# L298.net
KiCad netlist of a schematic drawn in EAGLE
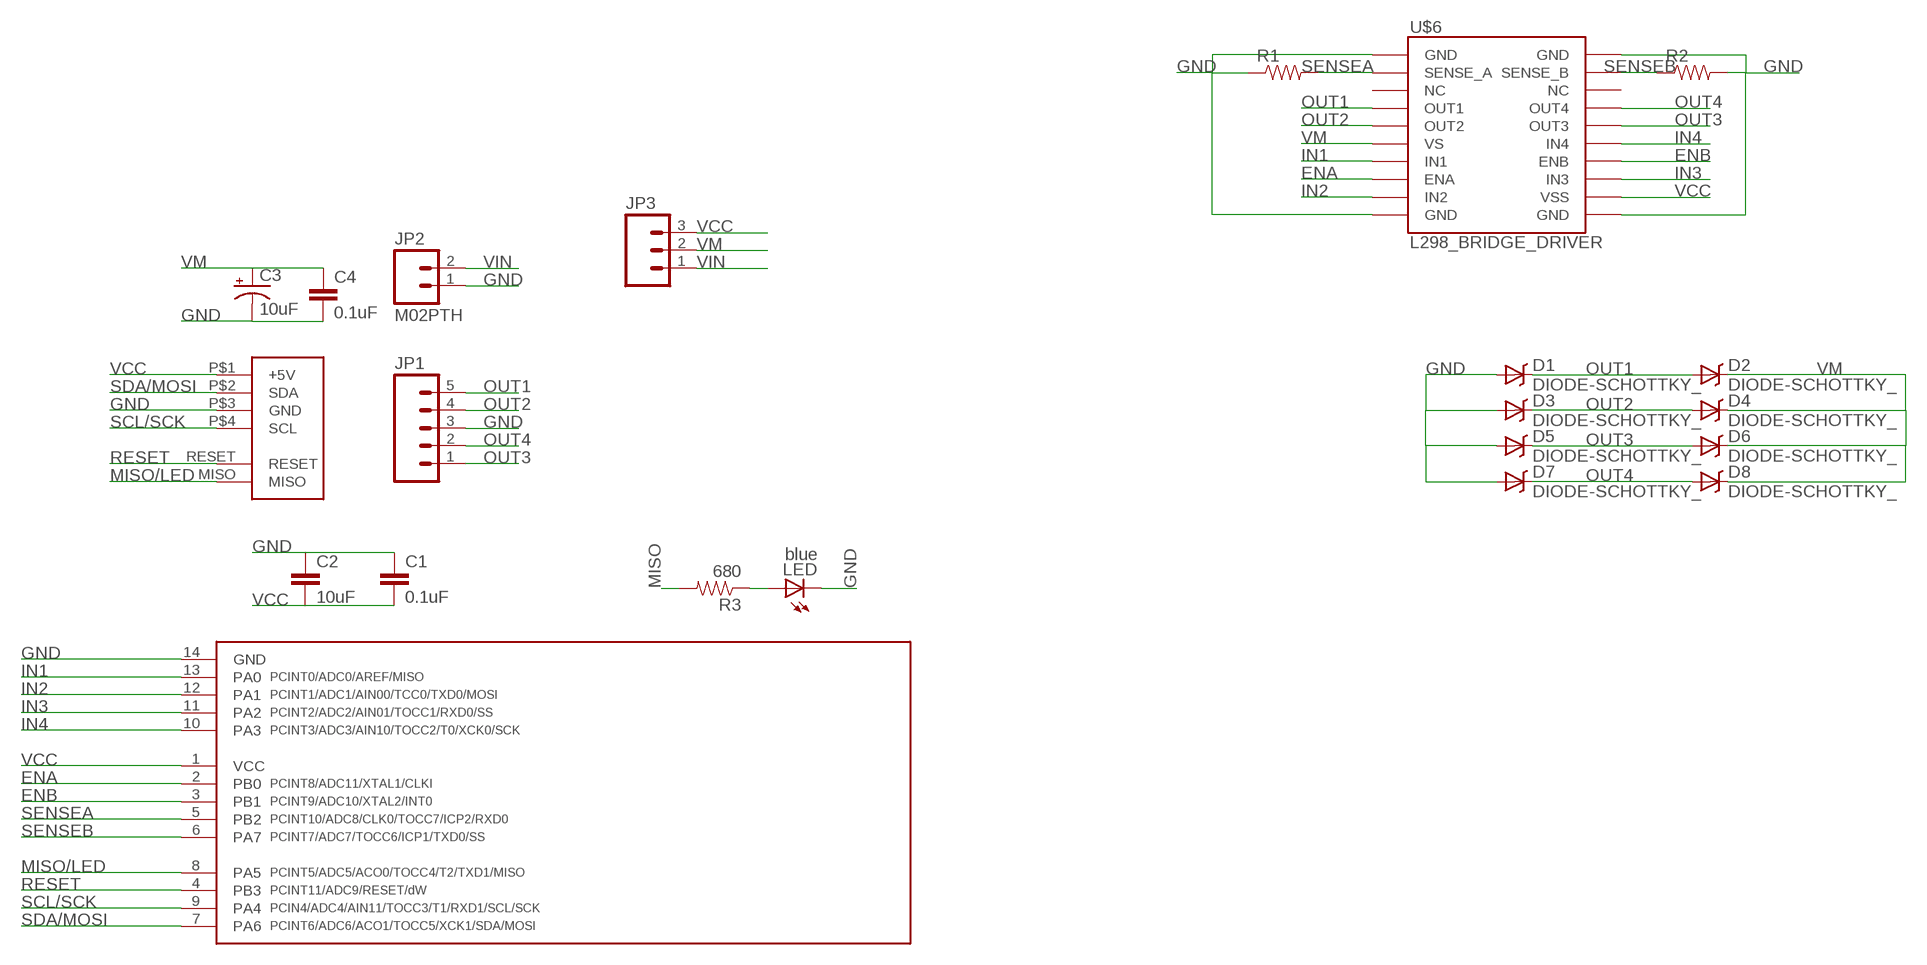
[diagram p0: schematic, sheet 1]

(export (version "E")
  (design (tool "Eeschema 10.0.6"))
  (components
    (comp (ref "C1")
      (value "0.1uF")
      (footprint "eagle-import:0805")
      (libsource (lib "eagle-import") (part "CAP0805"))
    )
    (comp (ref "C2")
      (value "10uF")
      (footprint "eagle-import:0805")
      (libsource (lib "eagle-import") (part "CAP0805"))
    )
    (comp (ref "C3")
      (value "10uF")
      (footprint "eagle-import:PANASONIC_D")
      (libsource (lib "eagle-import") (part "CAP_POLD"))
    )
    (comp (ref "C4")
      (value "0.1uF")
      (footprint "eagle-import:0805")
      (libsource (lib "eagle-import") (part "CAP0805"))
    )
    (comp (ref "D1")
      (value "DIODE-SCHOTTKY_")
      (footprint "eagle-import:SMA-DIODE")
      (libsource (lib "eagle-import") (part "DIODE-SCHOTTKY_"))
    )
    (comp (ref "D2")
      (value "DIODE-SCHOTTKY_")
      (footprint "eagle-import:SMA-DIODE")
      (libsource (lib "eagle-import") (part "DIODE-SCHOTTKY_"))
    )
    (comp (ref "D3")
      (value "DIODE-SCHOTTKY_")
      (footprint "eagle-import:SMA-DIODE")
      (libsource (lib "eagle-import") (part "DIODE-SCHOTTKY_"))
    )
    (comp (ref "D4")
      (value "DIODE-SCHOTTKY_")
      (footprint "eagle-import:SMA-DIODE")
      (libsource (lib "eagle-import") (part "DIODE-SCHOTTKY_"))
    )
    (comp (ref "D5")
      (value "DIODE-SCHOTTKY_")
      (footprint "eagle-import:SMA-DIODE")
      (libsource (lib "eagle-import") (part "DIODE-SCHOTTKY_"))
    )
    (comp (ref "D6")
      (value "DIODE-SCHOTTKY_")
      (footprint "eagle-import:SMA-DIODE")
      (libsource (lib "eagle-import") (part "DIODE-SCHOTTKY_"))
    )
    (comp (ref "D7")
      (value "DIODE-SCHOTTKY_")
      (footprint "eagle-import:SMA-DIODE")
      (libsource (lib "eagle-import") (part "DIODE-SCHOTTKY_"))
    )
    (comp (ref "D8")
      (value "DIODE-SCHOTTKY_")
      (footprint "eagle-import:SMA-DIODE")
      (libsource (lib "eagle-import") (part "DIODE-SCHOTTKY_"))
    )
    (comp (ref "JP1")
      (value "M05PTH")
      (footprint "eagle-import:1X05")
      (libsource (lib "eagle-import") (part "M05PTH"))
    )
    (comp (ref "JP2")
      (value "M02PTH")
      (footprint "eagle-import:1X02")
      (libsource (lib "eagle-import") (part "M02PTH"))
    )
    (comp (ref "JP3")
      (value "M03PTH")
      (footprint "eagle-import:1X03")
      (libsource (lib "eagle-import") (part "M03PTH"))
    )
    (comp (ref "LED")
      (value "blue")
      (footprint "eagle-import:CHIPLED_1206")
      (libsource (lib "eagle-import") (part "LEDCHIPLED_1206"))
    )
    (comp (ref "R1")
      (value "RESISTOR0805-RES")
      (footprint "eagle-import:0805")
      (libsource (lib "eagle-import") (part "SparkFun-Resistors_RESISTOR0805-RES"))
    )
    (comp (ref "R2")
      (value "RESISTOR0805-RES")
      (footprint "eagle-import:0805")
      (libsource (lib "eagle-import") (part "SparkFun-Resistors_RESISTOR0805-RES"))
    )
    (comp (ref "R3")
      (value "680")
      (footprint "eagle-import:0805")
      (libsource (lib "eagle-import") (part "RESISTOR0805-RES"))
    )
    (comp (ref "U$3")
      (value "TINY841")
      (footprint "eagle-import:SOIC14")
      (libsource (lib "eagle-import") (part "TINY841"))
    )
    (comp (ref "U$4")
      (value "FOOTPRINT")
      (footprint "eagle-import:FOOTPRINT")
      (libsource (lib "eagle-import") (part "FOOTPRINT"))
    )
    (comp (ref "U$6")
      (value "L298_BRIDGE_DRIVER")
      (footprint "eagle-import:POWERSO20")
      (libsource (lib "eagle-import") (part "L298_BRIDGE_DRIVER"))
    )
  )
  (nets
    (net (code "1") (name "/ENA") (class "Default")
      (node (ref "U$3") (pin "2") (pinfunction "PB0_2") (pintype "bidirectional"))
      (node (ref "U$6") (pin "8") (pinfunction "ENA_8") (pintype "bidirectional"))
    )
    (net (code "2") (name "/ENB") (class "Default")
      (node (ref "U$3") (pin "3") (pinfunction "PB1_3") (pintype "bidirectional"))
      (node (ref "U$6") (pin "14") (pinfunction "ENB_14") (pintype "bidirectional"))
    )
    (net (code "3") (name "/GND") (class "Default")
      (node (ref "C1") (pin "1") (pinfunction "1_1") (pintype "passive"))
      (node (ref "C2") (pin "1") (pinfunction "1_1") (pintype "passive"))
      (node (ref "C3") (pin "-") (pinfunction "-_-") (pintype "passive"))
      (node (ref "C4") (pin "2") (pinfunction "2_2") (pintype "passive"))
      (node (ref "D1") (pin "A") (pinfunction "A_A") (pintype "passive"))
      (node (ref "D3") (pin "A") (pinfunction "A_A") (pintype "passive"))
      (node (ref "D5") (pin "A") (pinfunction "A_A") (pintype "passive"))
      (node (ref "D7") (pin "A") (pinfunction "A_A") (pintype "passive"))
      (node (ref "JP1") (pin "3") (pinfunction "3_3") (pintype "passive"))
      (node (ref "JP2") (pin "1") (pinfunction "1_1") (pintype "passive"))
      (node (ref "LED") (pin "C") (pinfunction "C_C") (pintype "passive"))
      (node (ref "R1") (pin "1") (pinfunction "1_1") (pintype "passive"))
      (node (ref "R2") (pin "2") (pinfunction "2_2") (pintype "passive"))
      (node (ref "U$3") (pin "14") (pinfunction "GND_14") (pintype "bidirectional"))
      (node (ref "U$4") (pin "P$3") (pinfunction "GND_P$3") (pintype "power_in"))
      (node (ref "U$6") (pin "1") (pinfunction "GND_1") (pintype "bidirectional"))
      (node (ref "U$6") (pin "10") (pinfunction "GND_10") (pintype "bidirectional"))
      (node (ref "U$6") (pin "11") (pinfunction "GND_11") (pintype "bidirectional"))
      (node (ref "U$6") (pin "20") (pinfunction "GND_20") (pintype "bidirectional"))
    )
    (net (code "4") (name "/IN1") (class "Default")
      (node (ref "U$3") (pin "13") (pinfunction "PA0_13") (pintype "bidirectional"))
      (node (ref "U$6") (pin "7") (pinfunction "IN1_7") (pintype "bidirectional"))
    )
    (net (code "5") (name "/IN2") (class "Default")
      (node (ref "U$3") (pin "12") (pinfunction "PA1_12") (pintype "bidirectional"))
      (node (ref "U$6") (pin "9") (pinfunction "IN2_9") (pintype "bidirectional"))
    )
    (net (code "6") (name "/IN3") (class "Default")
      (node (ref "U$3") (pin "11") (pinfunction "PA2_11") (pintype "bidirectional"))
      (node (ref "U$6") (pin "13") (pinfunction "IN3_13") (pintype "bidirectional"))
    )
    (net (code "7") (name "/IN4") (class "Default")
      (node (ref "U$3") (pin "10") (pinfunction "PA3_10") (pintype "bidirectional"))
      (node (ref "U$6") (pin "15") (pinfunction "IN4_15") (pintype "bidirectional"))
    )
    (net (code "8") (name "/MISO") (class "Default")
      (node (ref "R3") (pin "2") (pinfunction "2_2") (pintype "passive"))
    )
    (net (code "9") (name "/MISO{slash}LED") (class "Default")
      (node (ref "U$3") (pin "8") (pinfunction "PA5_8") (pintype "bidirectional"))
      (node (ref "U$4") (pin "MISO") (pinfunction "MISO_MISO") (pintype "bidirectional"))
    )
    (net (code "10") (name "/OUT1") (class "Default")
      (node (ref "D1") (pin "C") (pinfunction "C_C") (pintype "passive"))
      (node (ref "D2") (pin "A") (pinfunction "A_A") (pintype "passive"))
      (node (ref "JP1") (pin "5") (pinfunction "5_5") (pintype "passive"))
      (node (ref "U$6") (pin "4") (pinfunction "OUT1_4") (pintype "bidirectional"))
    )
    (net (code "11") (name "/OUT2") (class "Default")
      (node (ref "D3") (pin "C") (pinfunction "C_C") (pintype "passive"))
      (node (ref "D4") (pin "A") (pinfunction "A_A") (pintype "passive"))
      (node (ref "JP1") (pin "4") (pinfunction "4_4") (pintype "passive"))
      (node (ref "U$6") (pin "5") (pinfunction "OUT2_5") (pintype "bidirectional"))
    )
    (net (code "12") (name "/OUT3") (class "Default")
      (node (ref "D5") (pin "C") (pinfunction "C_C") (pintype "passive"))
      (node (ref "D6") (pin "A") (pinfunction "A_A") (pintype "passive"))
      (node (ref "JP1") (pin "1") (pinfunction "1_1") (pintype "passive"))
      (node (ref "U$6") (pin "16") (pinfunction "OUT3_16") (pintype "bidirectional"))
    )
    (net (code "13") (name "/OUT4") (class "Default")
      (node (ref "D7") (pin "C") (pinfunction "C_C") (pintype "passive"))
      (node (ref "D8") (pin "A") (pinfunction "A_A") (pintype "passive"))
      (node (ref "JP1") (pin "2") (pinfunction "2_2") (pintype "passive"))
      (node (ref "U$6") (pin "17") (pinfunction "OUT4_17") (pintype "bidirectional"))
    )
    (net (code "14") (name "/RESET") (class "Default")
      (node (ref "U$3") (pin "4") (pinfunction "PB3_4") (pintype "bidirectional"))
      (node (ref "U$4") (pin "RESET") (pinfunction "RESET_RESET") (pintype "bidirectional"))
    )
    (net (code "15") (name "/SCL{slash}SCK") (class "Default")
      (node (ref "U$3") (pin "9") (pinfunction "PA4_9") (pintype "bidirectional"))
      (node (ref "U$4") (pin "P$4") (pinfunction "SCL_P$4") (pintype "bidirectional"))
    )
    (net (code "16") (name "/SDA{slash}MOSI") (class "Default")
      (node (ref "U$3") (pin "7") (pinfunction "PA6_7") (pintype "bidirectional"))
      (node (ref "U$4") (pin "P$2") (pinfunction "SDA_P$2") (pintype "bidirectional"))
    )
    (net (code "17") (name "/SENSEA") (class "Default")
      (node (ref "R1") (pin "2") (pinfunction "2_2") (pintype "passive"))
      (node (ref "U$3") (pin "5") (pinfunction "PB2_5") (pintype "bidirectional"))
      (node (ref "U$6") (pin "2") (pinfunction "SENSE_A_2") (pintype "bidirectional"))
    )
    (net (code "18") (name "/SENSEB") (class "Default")
      (node (ref "R2") (pin "1") (pinfunction "1_1") (pintype "passive"))
      (node (ref "U$3") (pin "6") (pinfunction "PA7_6") (pintype "bidirectional"))
      (node (ref "U$6") (pin "19") (pinfunction "SENSE_B_19") (pintype "bidirectional"))
    )
    (net (code "19") (name "/VCC") (class "Default")
      (node (ref "C1") (pin "2") (pinfunction "2_2") (pintype "passive"))
      (node (ref "C2") (pin "2") (pinfunction "2_2") (pintype "passive"))
      (node (ref "JP3") (pin "3") (pinfunction "3_3") (pintype "passive"))
      (node (ref "U$3") (pin "1") (pinfunction "VCC_1") (pintype "bidirectional"))
      (node (ref "U$4") (pin "P$1") (pinfunction "+5V_P$1") (pintype "power_in"))
      (node (ref "U$6") (pin "12") (pinfunction "VSS_12") (pintype "bidirectional"))
    )
    (net (code "20") (name "/VIN") (class "Default")
      (node (ref "JP2") (pin "2") (pinfunction "2_2") (pintype "passive"))
      (node (ref "JP3") (pin "1") (pinfunction "1_1") (pintype "passive"))
    )
    (net (code "21") (name "/VM") (class "Default")
      (node (ref "C3") (pin "+") (pinfunction "+_+") (pintype "passive"))
      (node (ref "C4") (pin "1") (pinfunction "1_1") (pintype "passive"))
      (node (ref "D2") (pin "C") (pinfunction "C_C") (pintype "passive"))
      (node (ref "D4") (pin "C") (pinfunction "C_C") (pintype "passive"))
      (node (ref "D6") (pin "C") (pinfunction "C_C") (pintype "passive"))
      (node (ref "D8") (pin "C") (pinfunction "C_C") (pintype "passive"))
      (node (ref "JP3") (pin "2") (pinfunction "2_2") (pintype "passive"))
      (node (ref "U$6") (pin "6") (pinfunction "VS_6") (pintype "bidirectional"))
    )
    (net (code "22") (name "Net-(LED-PadA)") (class "Default")
      (node (ref "LED") (pin "A") (pinfunction "A_A") (pintype "passive"))
      (node (ref "R3") (pin "1") (pinfunction "1_1") (pintype "passive"))
    )
    (net (code "23") (name "unconnected-(U$6-NC-Pad3)") (class "Default")
      (node (ref "U$6") (pin "3") (pinfunction "NC_3") (pintype "bidirectional"))
    )
    (net (code "24") (name "unconnected-(U$6-NC-Pad18)") (class "Default")
      (node (ref "U$6") (pin "18") (pinfunction "NC_18") (pintype "bidirectional"))
    )
  )
)
